# Power_Sources_2.net
KiCad netlist of a schematic drawn in Altium Designer
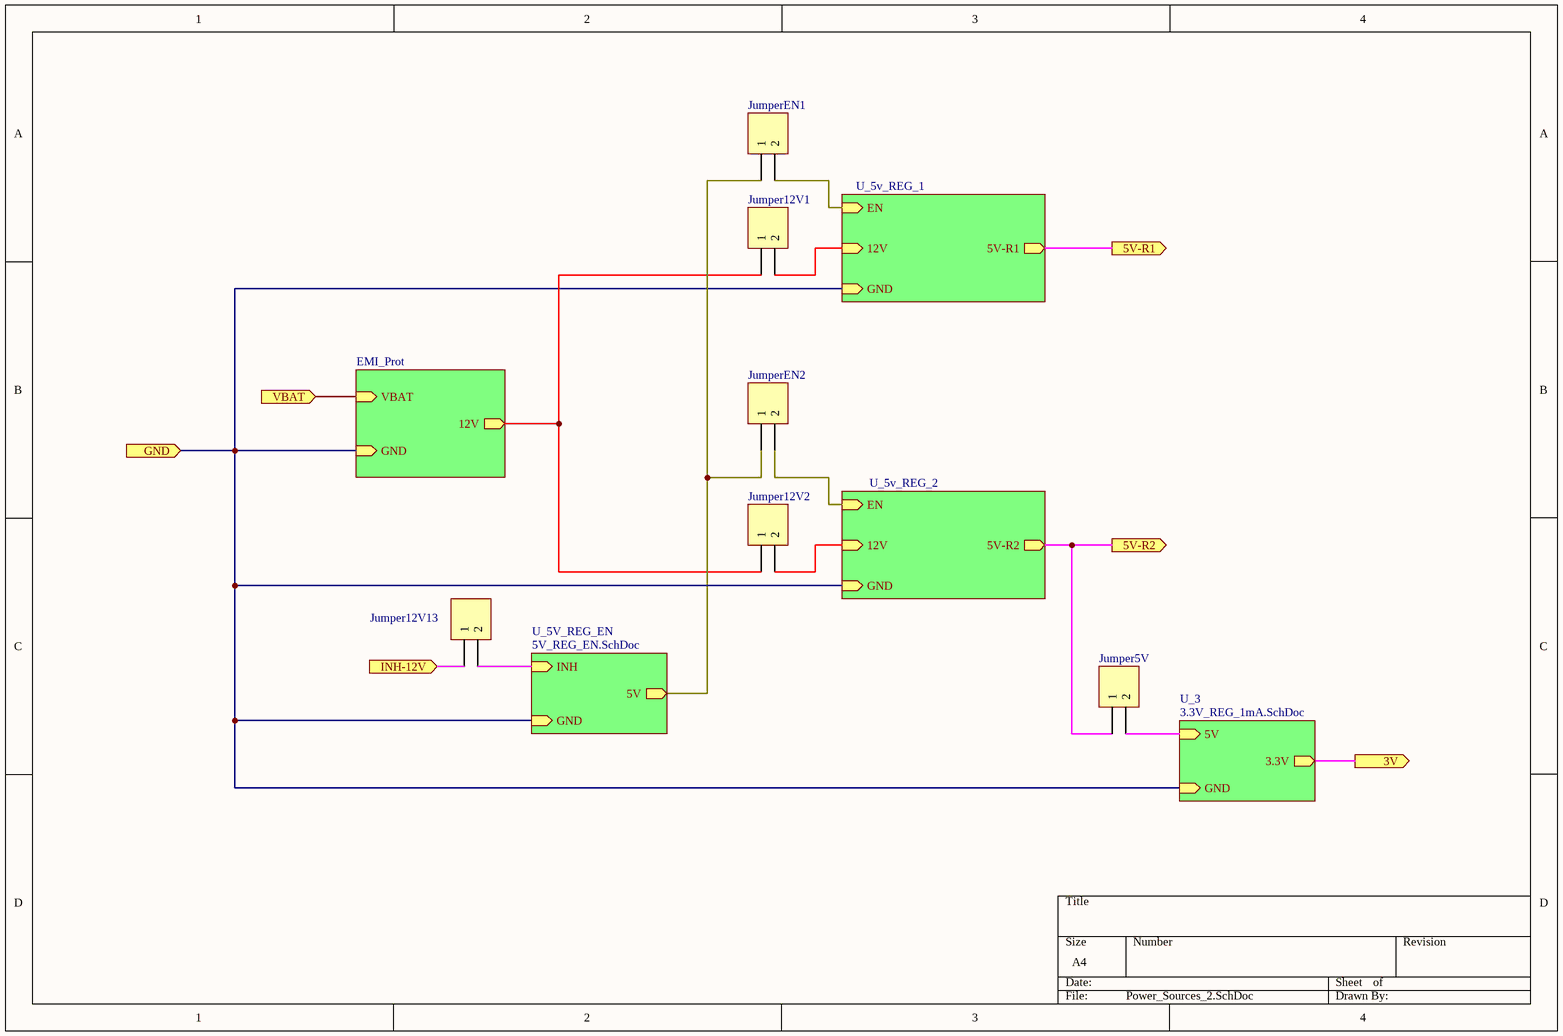
[diagram p0: Power_Sources_2.SchDoc]

(export (version "E")
  (design (tool "Eeschema 10.0.6"))
  (components
    (comp (ref "Jumper5V")
      (value "Header 2H")
      (footprint "HDR1X2H")
      (description "Header, 2-Pin, Right Angle")
      (fields (field (name "PUBLISHER") "Altium Limited"))
      (libsource (lib "Miscellaneous Connectors") (part "Header 2H"))
    )
    (comp (ref "Jumper12V1")
      (value "Header 2H")
      (footprint "HDR1X2H")
      (description "Header, 2-Pin, Right Angle")
      (fields (field (name "PUBLISHER") "Altium Limited"))
      (libsource (lib "Miscellaneous Connectors") (part "Header 2H"))
    )
    (comp (ref "Jumper12V2")
      (value "Header 2H")
      (footprint "HDR1X2H")
      (description "Header, 2-Pin, Right Angle")
      (fields (field (name "PUBLISHER") "Altium Limited"))
      (libsource (lib "Miscellaneous Connectors") (part "Header 2H"))
    )
    (comp (ref "Jumper12V13")
      (value "Header 2H")
      (footprint "HDR1X2H")
      (description "Header, 2-Pin, Right Angle")
      (fields (field (name "PUBLISHER") "Altium Limited"))
      (libsource (lib "Miscellaneous Connectors") (part "Header 2H"))
    )
    (comp (ref "JumperEN1")
      (value "Header 2H")
      (footprint "HDR1X2H")
      (description "Header, 2-Pin, Right Angle")
      (fields (field (name "PUBLISHER") "Altium Limited"))
      (libsource (lib "Miscellaneous Connectors") (part "Header 2H"))
    )
    (comp (ref "JumperEN2")
      (value "Header 2H")
      (footprint "HDR1X2H")
      (description "Header, 2-Pin, Right Angle")
      (fields (field (name "PUBLISHER") "Altium Limited"))
      (libsource (lib "Miscellaneous Connectors") (part "Header 2H"))
    )
  )
  (nets
    (net (code "2") (name "/5V") (class "Default")
      (node (ref "Jumper5V") (pin "2") (pinfunction "2_2") (pintype "passive"))
    )
    (net (code "4") (name "/5V-R2") (class "Default")
      (node (ref "Jumper5V") (pin "1") (pinfunction "1_1") (pintype "passive"))
    )
    (net (code "5") (name "/5V_1") (class "Default")
      (node (ref "JumperEN1") (pin "1") (pinfunction "1_1") (pintype "passive"))
      (node (ref "JumperEN2") (pin "1") (pinfunction "1_1") (pintype "passive"))
    )
    (net (code "6") (name "/12V") (class "Default")
      (node (ref "Jumper12V1") (pin "2") (pinfunction "2_2") (pintype "passive"))
    )
    (net (code "7") (name "/12V_1") (class "Default")
      (node (ref "Jumper12V1") (pin "1") (pinfunction "1_1") (pintype "passive"))
      (node (ref "Jumper12V2") (pin "1") (pinfunction "1_1") (pintype "passive"))
    )
    (net (code "8") (name "/12V_2") (class "Default")
      (node (ref "Jumper12V2") (pin "2") (pinfunction "2_2") (pintype "passive"))
    )
    (net (code "9") (name "/EN") (class "Default")
      (node (ref "JumperEN1") (pin "2") (pinfunction "2_2") (pintype "passive"))
    )
    (net (code "10") (name "/EN_1") (class "Default")
      (node (ref "JumperEN2") (pin "2") (pinfunction "2_2") (pintype "passive"))
    )
    (net (code "12") (name "/INH") (class "Default")
      (node (ref "Jumper12V13") (pin "2") (pinfunction "2_2") (pintype "passive"))
    )
    (net (code "13") (name "/INH-12V") (class "Default")
      (node (ref "Jumper12V13") (pin "1") (pinfunction "1_1") (pintype "passive"))
    )
  )
)
